# Schematic_v49.net
KiCad netlist of a schematic drawn in EAGLE
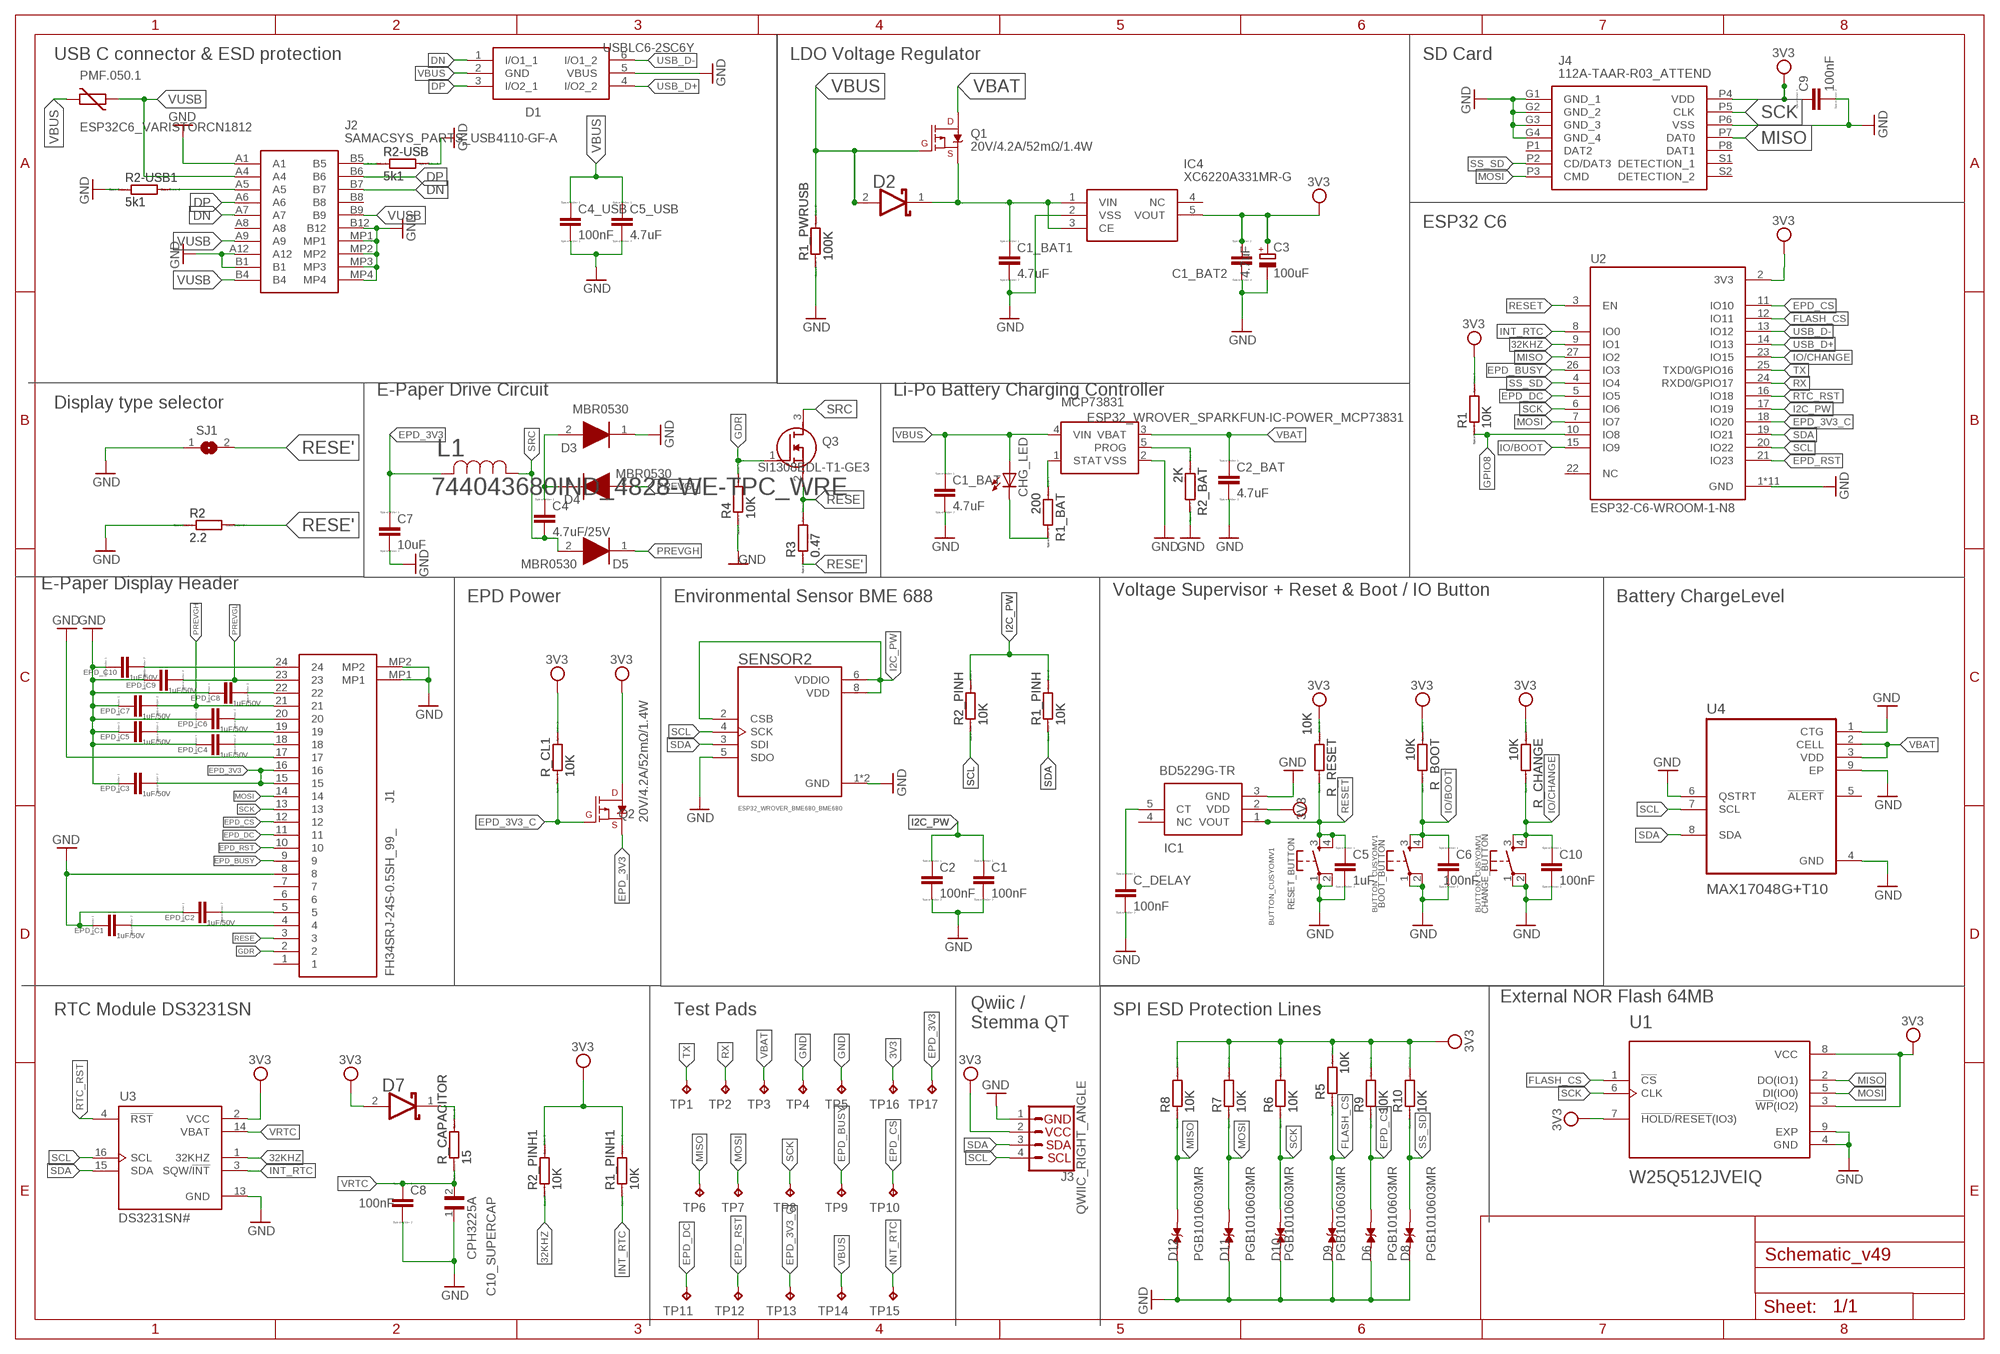
[diagram p0: schematic, sheet 1]

(export (version "E")
  (design (tool "Eeschema 10.0.6"))
  (components
    (comp (ref "BOOT_BUTTON")
      (value "BUTTON_CUSYOMV1")
      (footprint "eagle-import:MYBUTTON")
      (libsource (lib "eagle-import") (part "BUTTON_CUSYOMV1"))
    )
    (comp (ref "C1")
      (value "100nF")
      (footprint "eagle-import:EAGLE-LTSPICE_C0402")
      (libsource (lib "eagle-import") (part "ESP32_WROVER_EAGLE-LTSPICE_CC0402"))
    )
    (comp (ref "C1_BAT")
      (value "4.7uF")
      (footprint "eagle-import:EAGLE-LTSPICE_C0402")
      (libsource (lib "eagle-import") (part "ESP32_WROVER_EAGLE-LTSPICE_CC0402"))
    )
    (comp (ref "C1_BAT1")
      (value "4.7uF")
      (footprint "eagle-import:EAGLE-LTSPICE_C0402")
      (libsource (lib "eagle-import") (part "EAGLE-LTSPICE_CC0402"))
    )
    (comp (ref "C1_BAT2")
      (value "4.7uF")
      (footprint "eagle-import:EAGLE-LTSPICE_C0402")
      (libsource (lib "eagle-import") (part "EAGLE-LTSPICE_CC0402"))
    )
    (comp (ref "C2")
      (value "100nF")
      (footprint "eagle-import:EAGLE-LTSPICE_C0402")
      (libsource (lib "eagle-import") (part "ESP32_WROVER_EAGLE-LTSPICE_CC0402"))
    )
    (comp (ref "C2_BAT")
      (value "4.7uF")
      (footprint "eagle-import:EAGLE-LTSPICE_C0402")
      (libsource (lib "eagle-import") (part "ESP32_WROVER_EAGLE-LTSPICE_CC0402"))
    )
    (comp (ref "C3")
      (value "100uF")
      (footprint "eagle-import:RCL_CT3528")
      (libsource (lib "eagle-import") (part "RCL_CPOL-EUCT3528"))
    )
    (comp (ref "C4")
      (value "4.7uF/25V")
      (footprint "eagle-import:EAGLE-LTSPICE_C0402")
      (libsource (lib "eagle-import") (part "EAGLE-LTSPICE_CC0402"))
    )
    (comp (ref "C4_USB")
      (value "100nF")
      (footprint "eagle-import:EAGLE-LTSPICE_C0402")
      (libsource (lib "eagle-import") (part "EAGLE-LTSPICE_CC0402"))
    )
    (comp (ref "C5")
      (value "1uF")
      (footprint "eagle-import:EAGLE-LTSPICE_C0402")
      (libsource (lib "eagle-import") (part "EAGLE-LTSPICE_CC0402"))
    )
    (comp (ref "C5_USB")
      (value "4.7uF")
      (footprint "eagle-import:EAGLE-LTSPICE_C0402")
      (libsource (lib "eagle-import") (part "EAGLE-LTSPICE_CC0402"))
    )
    (comp (ref "C6")
      (value "100nF")
      (footprint "eagle-import:EAGLE-LTSPICE_C0402")
      (libsource (lib "eagle-import") (part "EAGLE-LTSPICE_CC0402"))
    )
    (comp (ref "C7")
      (value "10uF")
      (footprint "eagle-import:EAGLE-LTSPICE_C0402")
      (libsource (lib "eagle-import") (part "EAGLE-LTSPICE_CC0402"))
    )
    (comp (ref "C8")
      (value "100nF")
      (footprint "eagle-import:EAGLE-LTSPICE_C0402")
      (libsource (lib "eagle-import") (part "EAGLE-LTSPICE_CC0402"))
    )
    (comp (ref "C9")
      (value "100nF")
      (footprint "eagle-import:EAGLE-LTSPICE_C0402")
      (libsource (lib "eagle-import") (part "EAGLE-LTSPICE_CC0402"))
    )
    (comp (ref "C10")
      (value "100nF")
      (footprint "eagle-import:EAGLE-LTSPICE_C0402")
      (libsource (lib "eagle-import") (part "EAGLE-LTSPICE_CC0402"))
    )
    (comp (ref "C10_SUPERCAP")
      (value "CPH3225A")
      (footprint "eagle-import:CAPCP3225X100N")
      (fields (field (name "MF") "Seiko Instruments"))
      (libsource (lib "eagle-import") (part "CPH3225A"))
    )
    (comp (ref "CHANGE_BUTTON")
      (value "BUTTON_CUSYOMV1")
      (footprint "eagle-import:MYBUTTON")
      (libsource (lib "eagle-import") (part "BUTTON_CUSYOMV1"))
    )
    (comp (ref "CHG_LED")
      (value "ADAFRUIT_LEDCHIP-LED0603")
      (footprint "eagle-import:ADAFRUIT_CHIP-LED0603")
      (libsource (lib "eagle-import") (part "ADAFRUIT_LEDCHIP-LED0603"))
    )
    (comp (ref "C_DELAY")
      (value "100nF")
      (footprint "eagle-import:EAGLE-LTSPICE_C0402")
      (libsource (lib "eagle-import") (part "ESP32_WROVER_EAGLE-LTSPICE_CC0402"))
    )
    (comp (ref "D1")
      (value "USBLC6-2SC6Y")
      (footprint "eagle-import:SOT95P280X145-6N")
      (fields (field (name "MF") "STMicroelectronics"))
      (libsource (lib "eagle-import") (part "USBLC6-2SC6Y"))
    )
    (comp (ref "D2")
      (value "ESP32_WROVER_AVX---SD0805S020S1R0_AVX_SD0805S020S1R0_0_0AVX_SD0805S020S1R0_0_0")
      (footprint "eagle-import:ESP32_WROVER_AVX---SD0805S020S1R0_AVX_SD0805S020S1R0_0")
      (fields
        (field (name "DIGIKEY_PART_NUMBER") "478-7800-1-ND")
        (field (name "MF") "AVX")
        (field (name "MOUSER_PART_NUMBER") "581-SD0805S020S1R0")
      )
      (libsource (lib "eagle-import") (part "ESP32_WROVER_AVX---SD0805S020S1R0_AVX_SD0805S020S1R0_0_0AVX_SD0805S020S1R0_0_0"))
    )
    (comp (ref "D3")
      (value "MBR0530")
      (footprint "eagle-import:SOD3716X135N")
      (fields (field (name "MF") "ON Semiconductor"))
      (libsource (lib "eagle-import") (part "MBR0530"))
    )
    (comp (ref "D4")
      (value "MBR0530")
      (footprint "eagle-import:SOD3716X135N")
      (fields (field (name "MF") "ON Semiconductor"))
      (libsource (lib "eagle-import") (part "MBR0530"))
    )
    (comp (ref "D5")
      (value "MBR0530")
      (footprint "eagle-import:SOD3716X135N")
      (fields (field (name "MF") "ON Semiconductor"))
      (libsource (lib "eagle-import") (part "MBR0530"))
    )
    (comp (ref "D6")
      (value "PGB1010603MR")
      (footprint "eagle-import:DIOC1608X36N")
      (fields (field (name "MF") "Littelfuse Inc."))
      (libsource (lib "eagle-import") (part "PGB1010603MR"))
    )
    (comp (ref "D7")
      (value "ESP32_WROVER_AVX---SD0805S020S1R0_AVX_SD0805S020S1R0_0_0AVX_SD0805S020S1R0_0_0")
      (footprint "eagle-import:ESP32_WROVER_AVX---SD0805S020S1R0_AVX_SD0805S020S1R0_0")
      (fields
        (field (name "DIGIKEY_PART_NUMBER") "478-7800-1-ND")
        (field (name "MF") "AVX")
        (field (name "MOUSER_PART_NUMBER") "581-SD0805S020S1R0")
      )
      (libsource (lib "eagle-import") (part "ESP32_WROVER_AVX---SD0805S020S1R0_AVX_SD0805S020S1R0_0_0AVX_SD0805S020S1R0_0_0"))
    )
    (comp (ref "D8")
      (value "PGB1010603MR")
      (footprint "eagle-import:DIOC1608X36N")
      (fields (field (name "MF") "Littelfuse Inc."))
      (libsource (lib "eagle-import") (part "PGB1010603MR"))
    )
    (comp (ref "D9")
      (value "PGB1010603MR")
      (footprint "eagle-import:DIOC1608X36N")
      (fields (field (name "MF") "Littelfuse Inc."))
      (libsource (lib "eagle-import") (part "PGB1010603MR"))
    )
    (comp (ref "D10")
      (value "PGB1010603MR")
      (footprint "eagle-import:DIOC1608X36N")
      (fields (field (name "MF") "Littelfuse Inc."))
      (libsource (lib "eagle-import") (part "PGB1010603MR"))
    )
    (comp (ref "D11")
      (value "PGB1010603MR")
      (footprint "eagle-import:DIOC1608X36N")
      (fields (field (name "MF") "Littelfuse Inc."))
      (libsource (lib "eagle-import") (part "PGB1010603MR"))
    )
    (comp (ref "D12")
      (value "PGB1010603MR")
      (footprint "eagle-import:DIOC1608X36N")
      (fields (field (name "MF") "Littelfuse Inc."))
      (libsource (lib "eagle-import") (part "PGB1010603MR"))
    )
    (comp (ref "EPD_C1")
      (value "1uF/50V")
      (footprint "eagle-import:EAGLE-LTSPICE_C0402")
      (libsource (lib "eagle-import") (part "ESP32_WROVER_EAGLE-LTSPICE_CC0402"))
    )
    (comp (ref "EPD_C2")
      (value "1uF/50V")
      (footprint "eagle-import:EAGLE-LTSPICE_C0402")
      (libsource (lib "eagle-import") (part "ESP32_WROVER_EAGLE-LTSPICE_CC0402"))
    )
    (comp (ref "EPD_C3")
      (value "1uF/50V")
      (footprint "eagle-import:EAGLE-LTSPICE_C0402")
      (libsource (lib "eagle-import") (part "ESP32_WROVER_EAGLE-LTSPICE_CC0402"))
    )
    (comp (ref "EPD_C4")
      (value "1uF/50V")
      (footprint "eagle-import:EAGLE-LTSPICE_C0402")
      (libsource (lib "eagle-import") (part "ESP32_WROVER_EAGLE-LTSPICE_CC0402"))
    )
    (comp (ref "EPD_C5")
      (value "1uF/50V")
      (footprint "eagle-import:EAGLE-LTSPICE_C0402")
      (libsource (lib "eagle-import") (part "ESP32_WROVER_EAGLE-LTSPICE_CC0402"))
    )
    (comp (ref "EPD_C6")
      (value "1uF/50V")
      (footprint "eagle-import:EAGLE-LTSPICE_C0402")
      (libsource (lib "eagle-import") (part "ESP32_WROVER_EAGLE-LTSPICE_CC0402"))
    )
    (comp (ref "EPD_C7")
      (value "1uF/50V")
      (footprint "eagle-import:EAGLE-LTSPICE_C0402")
      (libsource (lib "eagle-import") (part "ESP32_WROVER_EAGLE-LTSPICE_CC0402"))
    )
    (comp (ref "EPD_C8")
      (value "1uF/50V")
      (footprint "eagle-import:EAGLE-LTSPICE_C0402")
      (libsource (lib "eagle-import") (part "ESP32_WROVER_EAGLE-LTSPICE_CC0402"))
    )
    (comp (ref "EPD_C9")
      (value "1uF/50V")
      (footprint "eagle-import:EAGLE-LTSPICE_C0402")
      (libsource (lib "eagle-import") (part "ESP32_WROVER_EAGLE-LTSPICE_CC0402"))
    )
    (comp (ref "EPD_C10")
      (value "1uF/50V")
      (footprint "eagle-import:EAGLE-LTSPICE_C0402")
      (libsource (lib "eagle-import") (part "ESP32_WROVER_EAGLE-LTSPICE_CC0402"))
    )
    (comp (ref "IC1")
      (value "BD5229G-TR")
      (footprint "eagle-import:SOT95P280X125-5N")
      (fields (field (name "MOUSER_PART_NUMBER") "755-BD5229G-TR"))
      (libsource (lib "eagle-import") (part "BD5229G-TR"))
    )
    (comp (ref "IC4")
      (value "XC6220A331MR-G")
      (footprint "eagle-import:SOT95P280X125-5N")
      (fields (field (name "MOUSER_PART_NUMBER") "865-XC6220A331MR-G"))
      (libsource (lib "eagle-import") (part "XC6220A331MR-G"))
    )
    (comp (ref "J1")
      (value "FH34SRJ-24S-0.5SH_99_")
      (footprint "eagle-import:FH34SRJ24S05SH99")
      (fields
        (field (name "MANUFACTURER_PART_NUMBER") "FH34SRJ-24S-0.5SH(99)")
        (field (name "MOUSER_PART_NUMBER") "798-FH34SRJ24S05SH99")
      )
      (libsource (lib "eagle-import") (part "FH34SRJ-24S-0.5SH_99_"))
    )
    (comp (ref "J2")
      (value "SAMACSYS_PARTS_USB4110-GF-A")
      (footprint "eagle-import:SAMACSYS_PARTS_USB4110GFA")
      (fields
        (field (name "MANUFACTURER_PART_NUMBER") "USB4110-GF-A")
        (field (name "MOUSER_PART_NUMBER") "640-USB4110-GF-A")
      )
      (libsource (lib "eagle-import") (part "SAMACSYS_PARTS_USB4110-GF-A"))
    )
    (comp (ref "J3")
      (value "QWIIC_RIGHT_ANGLE")
      (footprint "eagle-import:JST04_1MM_RA")
      (libsource (lib "eagle-import") (part "QWIIC_CONNECTORJS-1MM"))
    )
    (comp (ref "J4")
      (value "112A-TAAR-R03_ATTEND")
      (footprint "eagle-import:112ATAARR03ATTEND")
      (fields (field (name "MANUFACTURER_PART_NUMBER") "112A-TAAR-R03 ATTEND"))
      (libsource (lib "eagle-import") (part "112A-TAAR-R03_ATTEND"))
    )
    (comp (ref "L1")
      (value "744043680IND_4828-WE-TPC_WRE")
      (footprint "eagle-import:IND_4828-WE-TPC_WRE")
      (fields
        (field (name "MANUFACTURER_PART_NUMBER") "744043680")
        (field (name "COPYRIGHT") "Copyright (C) 2024 Ultra Librarian. All rights reserved.")
      )
      (libsource (lib "eagle-import") (part "744043680IND_4828-WE-TPC_WRE"))
    )
    (comp (ref "MCP73831")
      (value "ESP32_WROVER_SPARKFUN-IC-POWER_MCP73831")
      (footprint "eagle-import:ESP32_WROVER_SPARKFUN-IC-POWER_SOT23-5")
      (libsource (lib "eagle-import") (part "ESP32_WROVER_SPARKFUN-IC-POWER_MCP73831"))
    )
    (comp (ref "PMF.050.1")
      (value "ESP32C6_VARISTORCN1812")
      (footprint "eagle-import:ESP32C6_VARISTOR_CT_CN1812")
      (libsource (lib "eagle-import") (part "ESP32C6_VARISTORCN1812"))
    )
    (comp (ref "Q1")
      (value "20V/4.2A/52mΩ/1.4W")
      (footprint "eagle-import:ESP32_WROVER_SPARKFUN-DISCRETESEMI_SOT23-3")
      (libsource (lib "eagle-import") (part "ESP32_WROVER_SPARKFUN-DISCRETESEMI_MOSFET_PCH-DMG2305UX-7"))
    )
    (comp (ref "Q2")
      (value "20V/4.2A/52mΩ/1.4W")
      (footprint "eagle-import:ESP32_WROVER_SPARKFUN-DISCRETESEMI_SOT23-3")
      (libsource (lib "eagle-import") (part "ESP32_WROVER_SPARKFUN-DISCRETESEMI_MOSFET_PCH-DMG2305UX-7"))
    )
    (comp (ref "Q3")
      (value "SI1308EDL-T1-GE3")
      (footprint "eagle-import:SOT65P210X110-3N")
      (fields (field (name "MF") "Vishay Siliconix"))
      (libsource (lib "eagle-import") (part "SI1308EDL-T1-GE3"))
    )
    (comp (ref "R1")
      (value "10K")
      (footprint "eagle-import:ESP32_WROVER_EAGLE-LTSPICE_R0402")
      (libsource (lib "eagle-import") (part "ESP32_WROVER_EAGLE-LTSPICE_RR0402"))
    )
    (comp (ref "R1_BAT")
      (value "200")
      (footprint "eagle-import:ESP32_WROVER_EAGLE-LTSPICE_R0402")
      (libsource (lib "eagle-import") (part "ESP32_WROVER_EAGLE-LTSPICE_RR0402"))
    )
    (comp (ref "R1_PINH")
      (value "10K")
      (footprint "eagle-import:ESP32_WROVER_EAGLE-LTSPICE_R0402")
      (libsource (lib "eagle-import") (part "ESP32_WROVER_EAGLE-LTSPICE_RR0402"))
    )
    (comp (ref "R1_PINH1")
      (value "10K")
      (footprint "eagle-import:ESP32_WROVER_EAGLE-LTSPICE_R0402")
      (libsource (lib "eagle-import") (part "ESP32_WROVER_EAGLE-LTSPICE_RR0402"))
    )
    (comp (ref "R1_PWRUSB")
      (value "100K")
      (footprint "eagle-import:ESP32_WROVER_EAGLE-LTSPICE_R0402")
      (libsource (lib "eagle-import") (part "ESP32_WROVER_EAGLE-LTSPICE_RR0402"))
    )
    (comp (ref "R2")
      (value "2.2")
      (footprint "eagle-import:ESP32_WROVER_EAGLE-LTSPICE_R0402")
      (libsource (lib "eagle-import") (part "ESP32_WROVER_EAGLE-LTSPICE_RR0402"))
    )
    (comp (ref "R2-USB")
      (value "5k1")
      (footprint "eagle-import:ESP32_WROVER_EAGLE-LTSPICE_R0402")
      (libsource (lib "eagle-import") (part "ESP32_WROVER_EAGLE-LTSPICE_RR0402"))
    )
    (comp (ref "R2-USB1")
      (value "5k1")
      (footprint "eagle-import:ESP32_WROVER_EAGLE-LTSPICE_R0402")
      (libsource (lib "eagle-import") (part "ESP32_WROVER_EAGLE-LTSPICE_RR0402"))
    )
    (comp (ref "R2_BAT")
      (value "2K")
      (footprint "eagle-import:ESP32_WROVER_EAGLE-LTSPICE_R0402")
      (libsource (lib "eagle-import") (part "ESP32_WROVER_EAGLE-LTSPICE_RR0402"))
    )
    (comp (ref "R2_PINH")
      (value "10K")
      (footprint "eagle-import:ESP32_WROVER_EAGLE-LTSPICE_R0402")
      (libsource (lib "eagle-import") (part "ESP32_WROVER_EAGLE-LTSPICE_RR0402"))
    )
    (comp (ref "R2_PINH1")
      (value "10K")
      (footprint "eagle-import:ESP32_WROVER_EAGLE-LTSPICE_R0402")
      (libsource (lib "eagle-import") (part "ESP32_WROVER_EAGLE-LTSPICE_RR0402"))
    )
    (comp (ref "R3")
      (value "0.47")
      (footprint "eagle-import:ESP32_WROVER_EAGLE-LTSPICE_R0402")
      (libsource (lib "eagle-import") (part "ESP32_WROVER_EAGLE-LTSPICE_RR0402"))
    )
    (comp (ref "R4")
      (value "10K")
      (footprint "eagle-import:ESP32_WROVER_EAGLE-LTSPICE_R0402")
      (libsource (lib "eagle-import") (part "ESP32_WROVER_EAGLE-LTSPICE_RR0402"))
    )
    (comp (ref "R5")
      (value "10K")
      (footprint "eagle-import:ESP32_WROVER_EAGLE-LTSPICE_R0402")
      (libsource (lib "eagle-import") (part "ESP32_WROVER_EAGLE-LTSPICE_RR0402"))
    )
    (comp (ref "R6")
      (value "10K")
      (footprint "eagle-import:ESP32_WROVER_EAGLE-LTSPICE_R0402")
      (libsource (lib "eagle-import") (part "ESP32_WROVER_EAGLE-LTSPICE_RR0402"))
    )
    (comp (ref "R7")
      (value "10K")
      (footprint "eagle-import:ESP32_WROVER_EAGLE-LTSPICE_R0402")
      (libsource (lib "eagle-import") (part "ESP32_WROVER_EAGLE-LTSPICE_RR0402"))
    )
    (comp (ref "R8")
      (value "10K")
      (footprint "eagle-import:ESP32_WROVER_EAGLE-LTSPICE_R0402")
      (libsource (lib "eagle-import") (part "ESP32_WROVER_EAGLE-LTSPICE_RR0402"))
    )
    (comp (ref "R9")
      (value "10K")
      (footprint "eagle-import:ESP32_WROVER_EAGLE-LTSPICE_R0402")
      (libsource (lib "eagle-import") (part "ESP32_WROVER_EAGLE-LTSPICE_RR0402"))
    )
    (comp (ref "R10")
      (value "10K")
      (footprint "eagle-import:ESP32_WROVER_EAGLE-LTSPICE_R0402")
      (libsource (lib "eagle-import") (part "ESP32_WROVER_EAGLE-LTSPICE_RR0402"))
    )
    (comp (ref "RESET_BUTTON")
      (value "BUTTON_CUSYOMV1")
      (footprint "eagle-import:MYBUTTON")
      (libsource (lib "eagle-import") (part "BUTTON_CUSYOMV1"))
    )
    (comp (ref "R_BOOT")
      (value "10K")
      (footprint "eagle-import:ESP32_WROVER_EAGLE-LTSPICE_R0402")
      (libsource (lib "eagle-import") (part "ESP32_WROVER_EAGLE-LTSPICE_RR0402"))
    )
    (comp (ref "R_CAPACITOR")
      (value "15")
      (footprint "eagle-import:ESP32_WROVER_EAGLE-LTSPICE_R0402")
      (libsource (lib "eagle-import") (part "ESP32_WROVER_EAGLE-LTSPICE_RR0402"))
    )
    (comp (ref "R_CHANGE")
      (value "10K")
      (footprint "eagle-import:ESP32_WROVER_EAGLE-LTSPICE_R0402")
      (libsource (lib "eagle-import") (part "ESP32_WROVER_EAGLE-LTSPICE_RR0402"))
    )
    (comp (ref "R_CL1")
      (value "10K")
      (footprint "eagle-import:ESP32_WROVER_EAGLE-LTSPICE_R0402")
      (libsource (lib "eagle-import") (part "ESP32_WROVER_EAGLE-LTSPICE_RR0402"))
    )
    (comp (ref "R_RESET")
      (value "10K")
      (footprint "eagle-import:ESP32_WROVER_EAGLE-LTSPICE_R0402")
      (libsource (lib "eagle-import") (part "ESP32_WROVER_EAGLE-LTSPICE_RR0402"))
    )
    (comp (ref "SENSOR2")
      (value "ESP32_WROVER_BME680_BME680")
      (footprint "eagle-import:ESP32_WROVER_BME680_PSON80P300X300X100-8N")
      (fields (field (name "MF") "Bosch Sensortec") (field (name "MP") "BME680"))
      (libsource (lib "eagle-import") (part "ESP32_WROVER_BME680_BME680"))
    )
    (comp (ref "SJ1") (value "SJ") (footprint "eagle-import:SJ") (libsource (lib "eagle-import") (part "SJ")))
    (comp (ref "TP1")
      (value "TPTP20R")
      (footprint "eagle-import:TP20R")
      (libsource (lib "eagle-import") (part "TPTP20R"))
    )
    (comp (ref "TP2")
      (value "TPTP20R")
      (footprint "eagle-import:TP20R")
      (libsource (lib "eagle-import") (part "TPTP20R"))
    )
    (comp (ref "TP3")
      (value "TPTP20R")
      (footprint "eagle-import:TP20R")
      (libsource (lib "eagle-import") (part "TPTP20R"))
    )
    (comp (ref "TP4")
      (value "TPTP20R")
      (footprint "eagle-import:TP20R")
      (libsource (lib "eagle-import") (part "TPTP20R"))
    )
    (comp (ref "TP5")
      (value "TPTP20R")
      (footprint "eagle-import:TP20R")
      (libsource (lib "eagle-import") (part "TPTP20R"))
    )
    (comp (ref "TP6")
      (value "TPTP20R")
      (footprint "eagle-import:TP20R")
      (libsource (lib "eagle-import") (part "TPTP20R"))
    )
    (comp (ref "TP7")
      (value "TPTP20R")
      (footprint "eagle-import:TP20R")
      (libsource (lib "eagle-import") (part "TPTP20R"))
    )
    (comp (ref "TP8")
      (value "TPTP20R")
      (footprint "eagle-import:TP20R")
      (libsource (lib "eagle-import") (part "TPTP20R"))
    )
    (comp (ref "TP9")
      (value "TPTP20R")
      (footprint "eagle-import:TP20R")
      (libsource (lib "eagle-import") (part "TPTP20R"))
    )
    (comp (ref "TP10")
      (value "TPTP20R")
      (footprint "eagle-import:TP20R")
      (libsource (lib "eagle-import") (part "TPTP20R"))
    )
    (comp (ref "TP11")
      (value "TPTP20R")
      (footprint "eagle-import:TP20R")
      (libsource (lib "eagle-import") (part "TPTP20R"))
    )
    (comp (ref "TP12")
      (value "TPTP20R")
      (footprint "eagle-import:TP20R")
      (libsource (lib "eagle-import") (part "TPTP20R"))
    )
    (comp (ref "TP13")
      (value "TPTP20R")
      (footprint "eagle-import:TP20R")
      (libsource (lib "eagle-import") (part "TPTP20R"))
    )
    (comp (ref "TP14")
      (value "TPTP20R")
      (footprint "eagle-import:TP20R")
      (libsource (lib "eagle-import") (part "TPTP20R"))
    )
    (comp (ref "TP15")
      (value "TPTP20R")
      (footprint "eagle-import:TP20R")
      (libsource (lib "eagle-import") (part "TPTP20R"))
    )
    (comp (ref "TP16")
      (value "TPTP20R")
      (footprint "eagle-import:TP20R")
      (libsource (lib "eagle-import") (part "TPTP20R"))
    )
    (comp (ref "TP17")
      (value "TPTP20R")
      (footprint "eagle-import:TP20R")
      (libsource (lib "eagle-import") (part "TPTP20R"))
    )
    (comp (ref "U1")
      (value "W25Q512JVEIQ")
      (footprint "eagle-import:SON127P600X800X80-9N")
      (fields (field (name "MF") "Winbond Electronics"))
      (libsource (lib "eagle-import") (part "W25Q512JVEIQ"))
    )
    (comp (ref "U2")
      (value "ESP32-C6-WROOM-1-N8")
      (footprint "eagle-import:XCVR_ESP32-C6-WROOM-1-N8")
      (fields (field (name "MF") "Espressif Systems"))
      (libsource (lib "eagle-import") (part "ESP32-C6-WROOM-1-N8"))
    )
    (comp (ref "U3")
      (value "DS3231SN#")
      (footprint "eagle-import:SOIC127P1032X265-16N")
      (fields (field (name "MF") "Analog Devices"))
      (libsource (lib "eagle-import") (part "DS3231SN#"))
    )
    (comp (ref "U4")
      (value "MAX17048G+T10")
      (footprint "eagle-import:SON50P200X200X80-9N")
      (fields (field (name "MF") "Analog Devices"))
      (libsource (lib "eagle-import") (part "MAX17048G+T10"))
    )
  )
  (nets
    (net (code "1") (name "3V3") (class "Default")
      (node (ref "C1_BAT2") (pin "1") (pinfunction "1_1") (pintype "passive"))
      (node (ref "C3") (pin "+") (pinfunction "+_+") (pintype "passive"))
      (node (ref "C9") (pin "1") (pinfunction "1_1") (pintype "passive"))
      (node (ref "D7") (pin "2") (pinfunction "ANODE_2") (pintype "bidirectional"))
      (node (ref "IC1") (pin "2") (pinfunction "VDD_2") (pintype "bidirectional"))
      (node (ref "IC4") (pin "5") (pinfunction "VOUT_5") (pintype "bidirectional"))
      (node (ref "J3") (pin "2") (pinfunction "2_2") (pintype "power_in"))
      (node (ref "J4") (pin "P4") (pinfunction "VDD_P4") (pintype "bidirectional"))
      (node (ref "Q2") (pin "3") (pinfunction "D_3") (pintype "bidirectional"))
      (node (ref "R1") (pin "2") (pinfunction "2_2") (pintype "passive"))
      (node (ref "R10") (pin "2") (pinfunction "2_2") (pintype "passive"))
      (node (ref "R1_PINH1") (pin "2") (pinfunction "2_2") (pintype "passive"))
      (node (ref "R2_PINH1") (pin "2") (pinfunction "2_2") (pintype "passive"))
      (node (ref "R5") (pin "2") (pinfunction "2_2") (pintype "passive"))
      (node (ref "R6") (pin "2") (pinfunction "2_2") (pintype "passive"))
      (node (ref "R7") (pin "2") (pinfunction "2_2") (pintype "passive"))
      (node (ref "R8") (pin "2") (pinfunction "2_2") (pintype "passive"))
      (node (ref "R9") (pin "2") (pinfunction "2_2") (pintype "passive"))
      (node (ref "R_BOOT") (pin "1") (pinfunction "1_1") (pintype "passive"))
      (node (ref "R_CHANGE") (pin "1") (pinfunction "1_1") (pintype "passive"))
      (node (ref "R_CL1") (pin "2") (pinfunction "2_2") (pintype "passive"))
      (node (ref "R_RESET") (pin "1") (pinfunction "1_1") (pintype "passive"))
      (node (ref "TP16") (pin "TP") (pinfunction "TP_TP") (pintype "input"))
      (node (ref "U1") (pin "3") (pinfunction "~{WP}(IO2)_3") (pintype "bidirectional"))
      (node (ref "U1") (pin "7") (pinfunction "~{HOLD}/~{RESET}(IO3)_7") (pintype "bidirectional"))
      (node (ref "U1") (pin "8") (pinfunction "VCC_8") (pintype "power_in"))
      (node (ref "U2") (pin "2") (pinfunction "3V3_2") (pintype "power_in"))
      (node (ref "U3") (pin "2") (pinfunction "VCC_2") (pintype "power_in"))
    )
    (net (code "2") (name "32KHZ") (class "Default")
      (node (ref "R2_PINH1") (pin "1") (pinfunction "1_1") (pintype "passive"))
      (node (ref "U2") (pin "9") (pinfunction "IO1_9") (pintype "bidirectional"))
      (node (ref "U3") (pin "1") (pinfunction "32KHZ_1") (pintype "output"))
    )
    (net (code "3") (name "DN") (class "Default")
      (node (ref "D1") (pin "1") (pinfunction "I/O1_1_1") (pintype "bidirectional"))
      (node (ref "J2") (pin "A7") (pinfunction "A7_A7") (pintype "bidirectional"))
      (node (ref "J2") (pin "B7") (pinfunction "B7_B7") (pintype "bidirectional"))
    )
    (net (code "4") (name "DP") (class "Default")
      (node (ref "D1") (pin "3") (pinfunction "I/O2_1_3") (pintype "bidirectional"))
      (node (ref "J2") (pin "A6") (pinfunction "A6_A6") (pintype "bidirectional"))
      (node (ref "J2") (pin "B6") (pinfunction "B6_B6") (pintype "bidirectional"))
    )
    (net (code "5") (name "EPD_3V3") (class "Default")
      (node (ref "C7") (pin "1") (pinfunction "1_1") (pintype "passive"))
      (node (ref "EPD_C3") (pin "2") (pinfunction "2_2") (pintype "passive"))
      (node (ref "J1") (pin "15") (pinfunction "15_15") (pintype "bidirectional"))
      (node (ref "J1") (pin "16") (pinfunction "16_16") (pintype "bidirectional"))
      (node (ref "L1") (pin "2") (pinfunction "2_2") (pintype "passive"))
      (node (ref "Q2") (pin "2") (pinfunction "S_2") (pintype "bidirectional"))
      (node (ref "TP17") (pin "TP") (pinfunction "TP_TP") (pintype "input"))
    )
    (net (code "6") (name "EPD_3V3_C") (class "Default")
      (node (ref "Q2") (pin "1") (pinfunction "G_1") (pintype "bidirectional"))
      (node (ref "R_CL1") (pin "1") (pinfunction "1_1") (pintype "passive"))
      (node (ref "TP13") (pin "TP") (pinfunction "TP_TP") (pintype "input"))
      (node (ref "U2") (pin "18") (pinfunction "IO20_18") (pintype "bidirectional"))
    )
    (net (code "7") (name "EPD_BUSY") (class "Default")
      (node (ref "J1") (pin "9") (pinfunction "9_9") (pintype "bidirectional"))
      (node (ref "TP9") (pin "TP") (pinfunction "TP_TP") (pintype "input"))
      (node (ref "U2") (pin "26") (pinfunction "IO3_26") (pintype "bidirectional"))
    )
    (net (code "8") (name "EPD_CS") (class "Default")
      (node (ref "D6") (pin "2") (pinfunction "2_2") (pintype "passive"))
      (node (ref "J1") (pin "12") (pinfunction "12_12") (pintype "bidirectional"))
      (node (ref "R9") (pin "1") (pinfunction "1_1") (pintype "passive"))
      (node (ref "TP10") (pin "TP") (pinfunction "TP_TP") (pintype "input"))
      (node (ref "U2") (pin "11") (pinfunction "IO10_11") (pintype "bidirectional"))
    )
    (net (code "9") (name "EPD_DC") (class "Default")
      (node (ref "J1") (pin "11") (pinfunction "11_11") (pintype "bidirectional"))
      (node (ref "TP11") (pin "TP") (pinfunction "TP_TP") (pintype "input"))
      (node (ref "U2") (pin "5") (pinfunction "IO5_5") (pintype "bidirectional"))
    )
    (net (code "10") (name "EPD_RST") (class "Default")
      (node (ref "J1") (pin "10") (pinfunction "10_10") (pintype "bidirectional"))
      (node (ref "TP12") (pin "TP") (pinfunction "TP_TP") (pintype "input"))
      (node (ref "U2") (pin "21") (pinfunction "IO23_21") (pintype "bidirectional"))
    )
    (net (code "11") (name "FLASH_CS") (class "Default")
      (node (ref "D9") (pin "2") (pinfunction "2_2") (pintype "passive"))
      (node (ref "R5") (pin "1") (pinfunction "1_1") (pintype "passive"))
      (node (ref "U1") (pin "1") (pinfunction "~{CS}_1") (pintype "input"))
      (node (ref "U2") (pin "12") (pinfunction "IO11_12") (pintype "bidirectional"))
    )
    (net (code "12") (name "GDR") (class "Default")
      (node (ref "J1") (pin "2") (pinfunction "2_2") (pintype "bidirectional"))
      (node (ref "Q3") (pin "1") (pinfunction "G_1") (pintype "bidirectional"))
      (node (ref "R4") (pin "2") (pinfunction "2_2") (pintype "passive"))
    )
    (net (code "13") (name "GND") (class "Default")
      (node (ref "BOOT_BUTTON") (pin "1") (pinfunction "1_1") (pintype "passive"))
      (node (ref "BOOT_BUTTON") (pin "2") (pinfunction "2_2") (pintype "passive"))
      (node (ref "C1") (pin "2") (pinfunction "2_2") (pintype "passive"))
      (node (ref "C10") (pin "2") (pinfunction "2_2") (pintype "passive"))
      (node (ref "C10_SUPERCAP") (pin "1") (pinfunction "1_1") (pintype "passive"))
      (node (ref "C1_BAT") (pin "2") (pinfunction "2_2") (pintype "passive"))
      (node (ref "C1_BAT1") (pin "2") (pinfunction "2_2") (pintype "passive"))
      (node (ref "C1_BAT2") (pin "2") (pinfunction "2_2") (pintype "passive"))
      (node (ref "C2") (pin "2") (pinfunction "2_2") (pintype "passive"))
      (node (ref "C2_BAT") (pin "2") (pinfunction "2_2") (pintype "passive"))
      (node (ref "C3") (pin "-") (pinfunction "-_-") (pintype "passive"))
      (node (ref "C4_USB") (pin "2") (pinfunction "2_2") (pintype "passive"))
      (node (ref "C5") (pin "2") (pinfunction "2_2") (pintype "passive"))
      (node (ref "C5_USB") (pin "2") (pinfunction "2_2") (pintype "passive"))
      (node (ref "C6") (pin "2") (pinfunction "2_2") (pintype "passive"))
      (node (ref "C7") (pin "2") (pinfunction "2_2") (pintype "passive"))
      (node (ref "C8") (pin "2") (pinfunction "2_2") (pintype "passive"))
      (node (ref "C9") (pin "2") (pinfunction "2_2") (pintype "passive"))
      (node (ref "CHANGE_BUTTON") (pin "1") (pinfunction "1_1") (pintype "passive"))
      (node (ref "CHANGE_BUTTON") (pin "2") (pinfunction "2_2") (pintype "passive"))
      (node (ref "C_DELAY") (pin "2") (pinfunction "2_2") (pintype "passive"))
      (node (ref "D1") (pin "5") (pinfunction "VBUS_5") (pintype "bidirectional"))
      (node (ref "D10") (pin "1") (pinfunction "1_1") (pintype "passive"))
      (node (ref "D11") (pin "1") (pinfunction "1_1") (pintype "passive"))
      (node (ref "D12") (pin "1") (pinfunction "1_1") (pintype "passive"))
      (node (ref "D3") (pin "1") (pinfunction "K_1") (pintype "bidirectional"))
      (node (ref "D6") (pin "1") (pinfunction "1_1") (pintype "passive"))
      (node (ref "D8") (pin "1") (pinfunction "1_1") (pintype "passive"))
      (node (ref "D9") (pin "1") (pinfunction "1_1") (pintype "passive"))
      (node (ref "EPD_C1") (pin "1") (pinfunction "1_1") (pintype "passive"))
      (node (ref "EPD_C10") (pin "1") (pinfunction "1_1") (pintype "passive"))
      (node (ref "EPD_C2") (pin "1") (pinfunction "1_1") (pintype "passive"))
      (node (ref "EPD_C3") (pin "1") (pinfunction "1_1") (pintype "passive"))
      (node (ref "EPD_C4") (pin "1") (pinfunction "1_1") (pintype "passive"))
      (node (ref "EPD_C5") (pin "1") (pinfunction "1_1") (pintype "passive"))
      (node (ref "EPD_C6") (pin "1") (pinfunction "1_1") (pintype "passive"))
      (node (ref "EPD_C7") (pin "1") (pinfunction "1_1") (pintype "passive"))
      (node (ref "EPD_C8") (pin "1") (pinfunction "1_1") (pintype "passive"))
      (node (ref "EPD_C9") (pin "1") (pinfunction "1_1") (pintype "passive"))
      (node (ref "IC1") (pin "3") (pinfunction "GND_3") (pintype "bidirectional"))
      (node (ref "IC4") (pin "2") (pinfunction "VSS_2") (pintype "bidirectional"))
      (node (ref "J1") (pin "17") (pinfunction "17_17") (pintype "bidirectional"))
      (node (ref "J1") (pin "8") (pinfunction "8_8") (pintype "bidirectional"))
      (node (ref "J1") (pin "MP1") (pinfunction "MP1_MP1") (pintype "bidirectional"))
      (node (ref "J1") (pin "MP2") (pinfunction "MP2_MP2") (pintype "bidirectional"))
      (node (ref "J2") (pin "A1") (pinfunction "A1_A1") (pintype "bidirectional"))
      (node (ref "J2") (pin "A12") (pinfunction "A12_A12") (pintype "bidirectional"))
      (node (ref "J2") (pin "B1") (pinfunction "B1_B1") (pintype "bidirectional"))
      (node (ref "J2") (pin "B12") (pinfunction "B12_B12") (pintype "bidirectional"))
      (node (ref "J2") (pin "MP1") (pinfunction "MP1_MP1") (pintype "bidirectional"))
      (node (ref "J2") (pin "MP2") (pinfunction "MP2_MP2") (pintype "bidirectional"))
      (node (ref "J2") (pin "MP3") (pinfunction "MP3_MP3") (pintype "bidirectional"))
      (node (ref "J2") (pin "MP4") (pinfunction "MP4_MP4") (pintype "bidirectional"))
      (node (ref "J3") (pin "1") (pinfunction "1_1") (pintype "power_in"))
      (node (ref "J4") (pin "G1") (pinfunction "GND_1_G1") (pintype "bidirectional"))
      (node (ref "J4") (pin "G2") (pinfunction "GND_2_G2") (pintype "bidirectional"))
      (node (ref "J4") (pin "G3") (pinfunction "GND_3_G3") (pintype "bidirectional"))
      (node (ref "J4") (pin "G4") (pinfunction "GND_4_G4") (pintype "bidirectional"))
      (node (ref "J4") (pin "P6") (pinfunction "VSS_P6") (pintype "bidirectional"))
      (node (ref "MCP73831") (pin "2") (pinfunction "VSS_2") (pintype "power_in"))
      (node (ref "R1_PWRUSB") (pin "1") (pinfunction "1_1") (pintype "passive"))
      (node (ref "R2") (pin "1") (pinfunction "1_1") (pintype "passive"))
      (node (ref "R2-USB") (pin "2") (pinfunction "2_2") (pintype "passive"))
      (node (ref "R2-USB1") (pin "1") (pinfunction "1_1") (pintype "passive"))
      (node (ref "R2_BAT") (pin "2") (pinfunction "2_2") (pintype "passive"))
      (node (ref "R4") (pin "1") (pinfunction "1_1") (pintype "passive"))
      (node (ref "RESET_BUTTON") (pin "1") (pinfunction "1_1") (pintype "passive"))
      (node (ref "RESET_BUTTON") (pin "2") (pinfunction "2_2") (pintype "passive"))
      (node (ref "SENSOR2") (pin "1") (pinfunction "GND_1") (pintype "power_in"))
      (node (ref "SENSOR2") (pin "5") (pinfunction "SDO_5") (pintype "bidirectional"))
      (node (ref "SENSOR2") (pin "7") (pinfunction "GND_7") (pintype "power_in"))
      (node (ref "SJ1") (pin "1") (pinfunction "1_1") (pintype "passive"))
      (node (ref "TP4") (pin "TP") (pinfunction "TP_TP") (pintype "input"))
      (node (ref "TP5") (pin "TP") (pinfunction "TP_TP") (pintype "input"))
      (node (ref "U1") (pin "4") (pinfunction "GND_4") (pintype "power_in"))
      (node (ref "U1") (pin "9") (pinfunction "EXP_9") (pintype "passive"))
      (node (ref "U2") (pin "1") (pinfunction "GND_1") (pintype "power_in"))
      (node (ref "U2") (pin "28") (pinfunction "GND_28") (pintype "power_in"))
      (node (ref "U2") (pin "29_1") (pinfunction "GND_29_1") (pintype "power_in"))
      (node (ref "U2") (pin "29_2") (pinfunction "GND_29_2") (pintype "power_in"))
      (node (ref "U2") (pin "29_3") (pinfunction "GND_29_3") (pintype "power_in"))
      (node (ref "U2") (pin "29_4") (pinfunction "GND_29_4") (pintype "power_in"))
      (node (ref "U2") (pin "29_5") (pinfunction "GND_29_5") (pintype "power_in"))
      (node (ref "U2") (pin "29_6") (pinfunction "GND_29_6") (pintype "power_in"))
      (node (ref "U2") (pin "29_7") (pinfunction "GND_29_7") (pintype "power_in"))
      (node (ref "U2") (pin "29_8") (pinfunction "GND_29_8") (pintype "power_in"))
      (node (ref "U2") (pin "29_9") (pinfunction "GND_29_9") (pintype "power_in"))
      (node (ref "U3") (pin "13") (pinfunction "GND_13") (pintype "power_in"))
      (node (ref "U4") (pin "1") (pinfunction "CTG_1") (pintype "power_in"))
      (node (ref "U4") (pin "4") (pinfunction "GND_4") (pintype "power_in"))
      (node (ref "U4") (pin "6") (pinfunction "QSTRT_6") (pintype "input"))
      (node (ref "U4") (pin "9") (pinfunction "EP_9") (pintype "power_in"))
    )
    (net (code "14") (name "GPIO8") (class "Default")
      (node (ref "R1") (pin "1") (pinfunction "1_1") (pintype "passive"))
      (node (ref "U2") (pin "10") (pinfunction "IO8_10") (pintype "bidirectional"))
    )
    (net (code "15") (name "I2C_PW") (class "Default")
      (node (ref "C1") (pin "1") (pinfunction "1_1") (pintype "passive"))
      (node (ref "C2") (pin "1") (pinfunction "1_1") (pintype "passive"))
      (node (ref "R1_PINH") (pin "2") (pinfunction "2_2") (pintype "passive"))
      (node (ref "R2_PINH") (pin "2") (pinfunction "2_2") (pintype "passive"))
      (node (ref "SENSOR2") (pin "2") (pinfunction "CSB_2") (pintype "input"))
      (node (ref "SENSOR2") (pin "6") (pinfunction "VDDIO_6") (pintype "power_in"))
      (node (ref "SENSOR2") (pin "8") (pinfunction "VDD_8") (pintype "power_in"))
      (node (ref "U2") (pin "17") (pinfunction "IO19_17") (pintype "bidirectional"))
    )
    (net (code "16") (name "INT_RTC") (class "Default")
      (node (ref "R1_PINH1") (pin "1") (pinfunction "1_1") (pintype "passive"))
      (node (ref "TP15") (pin "TP") (pinfunction "TP_TP") (pintype "input"))
      (node (ref "U2") (pin "8") (pinfunction "IO0_8") (pintype "bidirectional"))
      (node (ref "U3") (pin "3") (pinfunction "SQW/~{INT}_3") (pintype "output"))
    )
    (net (code "17") (name "IO{slash}BOOT") (class "Default")
      (node (ref "BOOT_BUTTON") (pin "3") (pinfunction "3_3") (pintype "passive"))
      (node (ref "BOOT_BUTTON") (pin "4") (pinfunction "4_4") (pintype "passive"))
      (node (ref "C6") (pin "1") (pinfunction "1_1") (pintype "passive"))
      (node (ref "R_BOOT") (pin "2") (pinfunction "2_2") (pintype "passive"))
      (node (ref "U2") (pin "15") (pinfunction "IO9_15") (pintype "bidirectional"))
    )
    (net (code "18") (name "IO{slash}CHANGE") (class "Default")
      (node (ref "C10") (pin "1") (pinfunction "1_1") (pintype "passive"))
      (node (ref "CHANGE_BUTTON") (pin "3") (pinfunction "3_3") (pintype "passive"))
      (node (ref "CHANGE_BUTTON") (pin "4") (pinfunction "4_4") (pintype "passive"))
      (node (ref "R_CHANGE") (pin "2") (pinfunction "2_2") (pintype "passive"))
      (node (ref "U2") (pin "23") (pinfunction "IO15_23") (pintype "bidirectional"))
    )
    (net (code "19") (name "MISO") (class "Default")
      (node (ref "D12") (pin "2") (pinfunction "2_2") (pintype "passive"))
      (node (ref "J4") (pin "P7") (pinfunction "DAT0_P7") (pintype "bidirectional"))
      (node (ref "R8") (pin "1") (pinfunction "1_1") (pintype "passive"))
      (node (ref "TP6") (pin "TP") (pinfunction "TP_TP") (pintype "input"))
      (node (ref "U1") (pin "2") (pinfunction "DO(IO1)_2") (pintype "bidirectional"))
      (node (ref "U2") (pin "27") (pinfunction "IO2_27") (pintype "bidirectional"))
    )
    (net (code "20") (name "MOSI") (class "Default")
      (node (ref "D11") (pin "2") (pinfunction "2_2") (pintype "passive"))
      (node (ref "J1") (pin "14") (pinfunction "14_14") (pintype "bidirectional"))
      (node (ref "J4") (pin "P3") (pinfunction "CMD_P3") (pintype "bidirectional"))
      (node (ref "R7") (pin "1") (pinfunction "1_1") (pintype "passive"))
      (node (ref "TP7") (pin "TP") (pinfunction "TP_TP") (pintype "input"))
      (node (ref "U1") (pin "5") (pinfunction "DI(IO0)_5") (pintype "bidirectional"))
      (node (ref "U2") (pin "7") (pinfunction "IO7_7") (pintype "bidirectional"))
    )
    (net (code "21") (name "Net-(CHG_LED-PadC)") (class "Default")
      (node (ref "CHG_LED") (pin "C") (pinfunction "C_C") (pintype "passive"))
      (node (ref "R1_BAT") (pin "2") (pinfunction "2_2") (pintype "passive"))
    )
    (net (code "22") (name "Net-(D2-CATHODE)") (class "Default")
      (node (ref "C1_BAT1") (pin "1") (pinfunction "1_1") (pintype "passive"))
      (node (ref "D2") (pin "1") (pinfunction "CATHODE_1") (pintype "bidirectional"))
      (node (ref "IC4") (pin "1") (pinfunction "VIN_1") (pintype "bidirectional"))
      (node (ref "IC4") (pin "3") (pinfunction "CE_3") (pintype "bidirectional"))
      (node (ref "Q1") (pin "2") (pinfunction "S_2") (pintype "bidirectional"))
    )
    (net (code "23") (name "Net-(D3-A)") (class "Default")
      (node (ref "C4") (pin "1") (pinfunction "1_1") (pintype "passive"))
      (node (ref "D3") (pin "2") (pinfunction "A_2") (pintype "bidirectional"))
      (node (ref "D4") (pin "1") (pinfunction "K_1") (pintype "bidirectional"))
    )
    (net (code "24") (name "Net-(D7-CATHODE)") (class "Default")
      (node (ref "D7") (pin "1") (pinfunction "CATHODE_1") (pintype "bidirectional"))
      (node (ref "R_CAPACITOR") (pin "2") (pinfunction "2_2") (pintype "passive"))
    )
    (net (code "25") (name "Net-(EPD_C1-Pad2)") (class "Default")
      (node (ref "EPD_C1") (pin "2") (pinfunction "2_2") (pintype "passive"))
      (node (ref "J1") (pin "4") (pinfunction "4_4") (pintype "bidirectional"))
    )
    (net (code "26") (name "Net-(EPD_C2-Pad2)") (class "Default")
      (node (ref "EPD_C2") (pin "2") (pinfunction "2_2") (pintype "passive"))
      (node (ref "J1") (pin "5") (pinfunction "5_5") (pintype "bidirectional"))
    )
    (net (code "27") (name "Net-(EPD_C4-Pad2)") (class "Default")
      (node (ref "EPD_C4") (pin "2") (pinfunction "2_2") (pintype "passive"))
      (node (ref "J1") (pin "18") (pinfunction "18_18") (pintype "bidirectional"))
    )
    (net (code "28") (name "Net-(EPD_C5-Pad2)") (class "Default")
      (node (ref "EPD_C5") (pin "2") (pinfunction "2_2") (pintype "passive"))
      (node (ref "J1") (pin "19") (pinfunction "19_19") (pintype "bidirectional"))
    )
    (net (code "29") (name "Net-(EPD_C6-Pad2)") (class "Default")
      (node (ref "EPD_C6") (pin "2") (pinfunction "2_2") (pintype "passive"))
      (node (ref "J1") (pin "20") (pinfunction "20_20") (pintype "bidirectional"))
    )
    (net (code "30") (name "Net-(EPD_C8-Pad2)") (class "Default")
      (node (ref "EPD_C8") (pin "2") (pinfunction "2_2") (pintype "passive"))
      (node (ref "J1") (pin "22") (pinfunction "22_22") (pintype "bidirectional"))
    )
    (net (code "31") (name "Net-(EPD_C10-Pad2)") (class "Default")
      (node (ref "EPD_C10") (pin "2") (pinfunction "2_2") (pintype "passive"))
      (node (ref "J1") (pin "24") (pinfunction "24_24") (pintype "bidirectional"))
    )
    (net (code "32") (name "Net-(IC1-CT)") (class "Default")
      (node (ref "C_DELAY") (pin "1") (pinfunction "1_1") (pintype "passive"))
      (node (ref "IC1") (pin "5") (pinfunction "CT_5") (pintype "bidirectional"))
    )
    (net (code "33") (name "Net-(J2-PadA5)") (class "Default")
      (node (ref "J2") (pin "A5") (pinfunction "A5_A5") (pintype "bidirectional"))
      (node (ref "R2-USB1") (pin "2") (pinfunction "2_2") (pintype "passive"))
    )
    (net (code "34") (name "Net-(J2-PadB5)") (class "Default")
      (node (ref "J2") (pin "B5") (pinfunction "B5_B5") (pintype "bidirectional"))
      (node (ref "R2-USB") (pin "1") (pinfunction "1_1") (pintype "passive"))
    )
    (net (code "35") (name "Net-(MCP73831-PROG)") (class "Default")
      (node (ref "MCP73831") (pin "5") (pinfunction "PROG_5") (pintype "input"))
      (node (ref "R2_BAT") (pin "1") (pinfunction "1_1") (pintype "passive"))
    )
    (net (code "36") (name "Net-(MCP73831-STAT)") (class "Default")
      (node (ref "MCP73831") (pin "1") (pinfunction "STAT_1") (pintype "output"))
      (node (ref "R1_BAT") (pin "1") (pinfunction "1_1") (pintype "passive"))
    )
    (net (code "37") (name "PREVGH") (class "Default")
      (node (ref "D5") (pin "1") (pinfunction "K_1") (pintype "bidirectional"))
      (node (ref "EPD_C7") (pin "2") (pinfunction "2_2") (pintype "passive"))
      (node (ref "J1") (pin "21") (pinfunction "21_21") (pintype "bidirectional"))
    )
    (net (code "38") (name "PREVGL") (class "Default")
      (node (ref "D4") (pin "2") (pinfunction "A_2") (pintype "bidirectional"))
      (node (ref "EPD_C9") (pin "2") (pinfunction "2_2") (pintype "passive"))
      (node (ref "J1") (pin "23") (pinfunction "23_23") (pintype "bidirectional"))
    )
    (net (code "39") (name "RESE") (class "Default")
      (node (ref "J1") (pin "3") (pinfunction "3_3") (pintype "bidirectional"))
      (node (ref "Q3") (pin "2") (pinfunction "S_2") (pintype "bidirectional"))
      (node (ref "R3") (pin "2") (pinfunction "2_2") (pintype "passive"))
    )
    (net (code "40") (name "RESE'") (class "Default")
      (node (ref "R2") (pin "2") (pinfunction "2_2") (pintype "passive"))
      (node (ref "R3") (pin "1") (pinfunction "1_1") (pintype "passive"))
      (node (ref "SJ1") (pin "2") (pinfunction "2_2") (pintype "passive"))
    )
    (net (code "41") (name "RESET") (class "Default")
      (node (ref "C5") (pin "1") (pinfunction "1_1") (pintype "passive"))
      (node (ref "IC1") (pin "1") (pinfunction "VOUT_1") (pintype "bidirectional"))
      (node (ref "RESET_BUTTON") (pin "3") (pinfunction "3_3") (pintype "passive"))
      (node (ref "RESET_BUTTON") (pin "4") (pinfunction "4_4") (pintype "passive"))
      (node (ref "R_RESET") (pin "2") (pinfunction "2_2") (pintype "passive"))
      (node (ref "U2") (pin "3") (pinfunction "EN_3") (pintype "input"))
    )
    (net (code "42") (name "RTC_RST") (class "Default")
      (node (ref "U2") (pin "16") (pinfunction "IO18_16") (pintype "bidirectional"))
      (node (ref "U3") (pin "4") (pinfunction "~{RST}_4") (pintype "input"))
    )
    (net (code "43") (name "RX") (class "Default")
      (node (ref "TP2") (pin "TP") (pinfunction "TP_TP") (pintype "input"))
      (node (ref "U2") (pin "24") (pinfunction "RXD0/GPIO17_24") (pintype "bidirectional"))
    )
    (net (code "44") (name "SCK") (class "Default")
      (node (ref "D10") (pin "2") (pinfunction "2_2") (pintype "passive"))
      (node (ref "J1") (pin "13") (pinfunction "13_13") (pintype "bidirectional"))
      (node (ref "J4") (pin "P5") (pinfunction "CLK_P5") (pintype "bidirectional"))
      (node (ref "R6") (pin "1") (pinfunction "1_1") (pintype "passive"))
      (node (ref "TP8") (pin "TP") (pinfunction "TP_TP") (pintype "input"))
      (node (ref "U1") (pin "6") (pinfunction "CLK_6") (pintype "input"))
      (node (ref "U2") (pin "6") (pinfunction "IO6_6") (pintype "bidirectional"))
    )
    (net (code "45") (name "SCL") (class "Default")
      (node (ref "J3") (pin "4") (pinfunction "4_4") (pintype "passive"))
      (node (ref "R2_PINH") (pin "1") (pinfunction "1_1") (pintype "passive"))
      (node (ref "SENSOR2") (pin "4") (pinfunction "SCK_4") (pintype "input"))
      (node (ref "U2") (pin "20") (pinfunction "IO22_20") (pintype "bidirectional"))
      (node (ref "U3") (pin "16") (pinfunction "SCL_16") (pintype "input"))
      (node (ref "U4") (pin "7") (pinfunction "SCL_7") (pintype "input"))
    )
    (net (code "46") (name "SDA") (class "Default")
      (node (ref "J3") (pin "3") (pinfunction "3_3") (pintype "passive"))
      (node (ref "R1_PINH") (pin "1") (pinfunction "1_1") (pintype "passive"))
      (node (ref "SENSOR2") (pin "3") (pinfunction "SDI_3") (pintype "bidirectional"))
      (node (ref "U2") (pin "19") (pinfunction "IO21_19") (pintype "bidirectional"))
      (node (ref "U3") (pin "15") (pinfunction "SDA_15") (pintype "bidirectional"))
      (node (ref "U4") (pin "8") (pinfunction "SDA_8") (pintype "bidirectional"))
    )
    (net (code "47") (name "SRC") (class "Default")
      (node (ref "C4") (pin "2") (pinfunction "2_2") (pintype "passive"))
      (node (ref "D5") (pin "2") (pinfunction "A_2") (pintype "bidirectional"))
      (node (ref "L1") (pin "1") (pinfunction "1_1") (pintype "passive"))
      (node (ref "Q3") (pin "3") (pinfunction "D_3") (pintype "bidirectional"))
    )
    (net (code "48") (name "SS_SD") (class "Default")
      (node (ref "D8") (pin "2") (pinfunction "2_2") (pintype "passive"))
      (node (ref "J4") (pin "P2") (pinfunction "CD/DAT3_P2") (pintype "bidirectional"))
      (node (ref "R10") (pin "1") (pinfunction "1_1") (pintype "passive"))
      (node (ref "U2") (pin "4") (pinfunction "IO4_4") (pintype "bidirectional"))
    )
    (net (code "49") (name "TX") (class "Default")
      (node (ref "TP1") (pin "TP") (pinfunction "TP_TP") (pintype "input"))
      (node (ref "U2") (pin "25") (pinfunction "TXD0/GPIO16_25") (pintype "bidirectional"))
    )
    (net (code "50") (name "USB_D+") (class "Default")
      (node (ref "D1") (pin "4") (pinfunction "I/O2_2_4") (pintype "bidirectional"))
      (node (ref "U2") (pin "14") (pinfunction "IO13_14") (pintype "bidirectional"))
    )
    (net (code "51") (name "USB_D-") (class "Default")
      (node (ref "D1") (pin "6") (pinfunction "I/O1_2_6") (pintype "bidirectional"))
      (node (ref "U2") (pin "13") (pinfunction "IO12_13") (pintype "bidirectional"))
    )
    (net (code "52") (name "VBAT") (class "Default")
      (node (ref "C2_BAT") (pin "1") (pinfunction "1_1") (pintype "passive"))
      (node (ref "MCP73831") (pin "3") (pinfunction "VBAT_3") (pintype "power_in"))
      (node (ref "Q1") (pin "3") (pinfunction "D_3") (pintype "bidirectional"))
      (node (ref "TP3") (pin "TP") (pinfunction "TP_TP") (pintype "input"))
      (node (ref "U4") (pin "2") (pinfunction "CELL_2") (pintype "power_in"))
      (node (ref "U4") (pin "3") (pinfunction "VDD_3") (pintype "power_in"))
    )
    (net (code "53") (name "VBUS") (class "Default")
      (node (ref "C1_BAT") (pin "1") (pinfunction "1_1") (pintype "passive"))
      (node (ref "C4_USB") (pin "1") (pinfunction "1_1") (pintype "passive"))
      (node (ref "C5_USB") (pin "1") (pinfunction "1_1") (pintype "passive"))
      (node (ref "CHG_LED") (pin "A") (pinfunction "A_A") (pintype "passive"))
      (node (ref "D1") (pin "2") (pinfunction "GND_2") (pintype "bidirectional"))
      (node (ref "D2") (pin "2") (pinfunction "ANODE_2") (pintype "bidirectional"))
      (node (ref "MCP73831") (pin "4") (pinfunction "VIN_4") (pintype "power_in"))
      (node (ref "PMF.050.1") (pin "2") (pinfunction "2_2") (pintype "passive"))
      (node (ref "Q1") (pin "1") (pinfunction "G_1") (pintype "bidirectional"))
      (node (ref "R1_PWRUSB") (pin "2") (pinfunction "2_2") (pintype "passive"))
      (node (ref "TP14") (pin "TP") (pinfunction "TP_TP") (pintype "input"))
    )
    (net (code "54") (name "VRTC") (class "Default")
      (node (ref "C10_SUPERCAP") (pin "2") (pinfunction "2_2") (pintype "passive"))
      (node (ref "C8") (pin "1") (pinfunction "1_1") (pintype "passive"))
      (node (ref "R_CAPACITOR") (pin "1") (pinfunction "1_1") (pintype "passive"))
      (node (ref "U3") (pin "14") (pinfunction "VBAT_14") (pintype "power_in"))
    )
    (net (code "55") (name "VUSB") (class "Default")
      (node (ref "J2") (pin "A4") (pinfunction "A4_A4") (pintype "bidirectional"))
      (node (ref "J2") (pin "A9") (pinfunction "A9_A9") (pintype "bidirectional"))
      (node (ref "J2") (pin "B4") (pinfunction "B4_B4") (pintype "bidirectional"))
      (node (ref "J2") (pin "B9") (pinfunction "B9_B9") (pintype "bidirectional"))
      (node (ref "PMF.050.1") (pin "1") (pinfunction "1_1") (pintype "passive"))
    )
    (net (code "56") (name "unconnected-(IC1-NC-Pad4)") (class "Default")
      (node (ref "IC1") (pin "4") (pinfunction "NC_4") (pintype "no_connect"))
    )
    (net (code "57") (name "unconnected-(IC4-NC-Pad4)") (class "Default")
      (node (ref "IC4") (pin "4") (pinfunction "NC_4") (pintype "no_connect"))
    )
    (net (code "58") (name "unconnected-(J1-Pad1)") (class "Default")
      (node (ref "J1") (pin "1") (pinfunction "1_1") (pintype "bidirectional"))
    )
    (net (code "59") (name "unconnected-(J1-Pad6)") (class "Default")
      (node (ref "J1") (pin "6") (pinfunction "6_6") (pintype "bidirectional"))
    )
    (net (code "60") (name "unconnected-(J1-Pad7)") (class "Default")
      (node (ref "J1") (pin "7") (pinfunction "7_7") (pintype "bidirectional"))
    )
    (net (code "61") (name "unconnected-(J2-PadA8)") (class "Default")
      (node (ref "J2") (pin "A8") (pinfunction "A8_A8") (pintype "bidirectional"))
    )
    (net (code "62") (name "unconnected-(J2-PadB8)") (class "Default")
      (node (ref "J2") (pin "B8") (pinfunction "B8_B8") (pintype "bidirectional"))
    )
    (net (code "63") (name "unconnected-(J4-DAT1-PadP8)") (class "Default")
      (node (ref "J4") (pin "P8") (pinfunction "DAT1_P8") (pintype "bidirectional"))
    )
    (net (code "64") (name "unconnected-(J4-DAT2-PadP1)") (class "Default")
      (node (ref "J4") (pin "P1") (pinfunction "DAT2_P1") (pintype "bidirectional"))
    )
    (net (code "65") (name "unconnected-(J4-DETECTION_1-PadS1)") (class "Default")
      (node (ref "J4") (pin "S1") (pinfunction "DETECTION_1_S1") (pintype "bidirectional"))
    )
    (net (code "66") (name "unconnected-(J4-DETECTION_2-PadS2)") (class "Default")
      (node (ref "J4") (pin "S2") (pinfunction "DETECTION_2_S2") (pintype "bidirectional"))
    )
    (net (code "67") (name "unconnected-(U2-NC-Pad22)") (class "Default")
      (node (ref "U2") (pin "22") (pinfunction "NC_22") (pintype "no_connect"))
    )
    (net (code "68") (name "unconnected-(U4-~{ALERT}-Pad5)") (class "Default")
      (node (ref "U4") (pin "5") (pinfunction "~{ALERT}_5") (pintype "output"))
    )
  )
)
